# band-dsp-micro.net
KiCad netlist of a schematic drawn in EAGLE
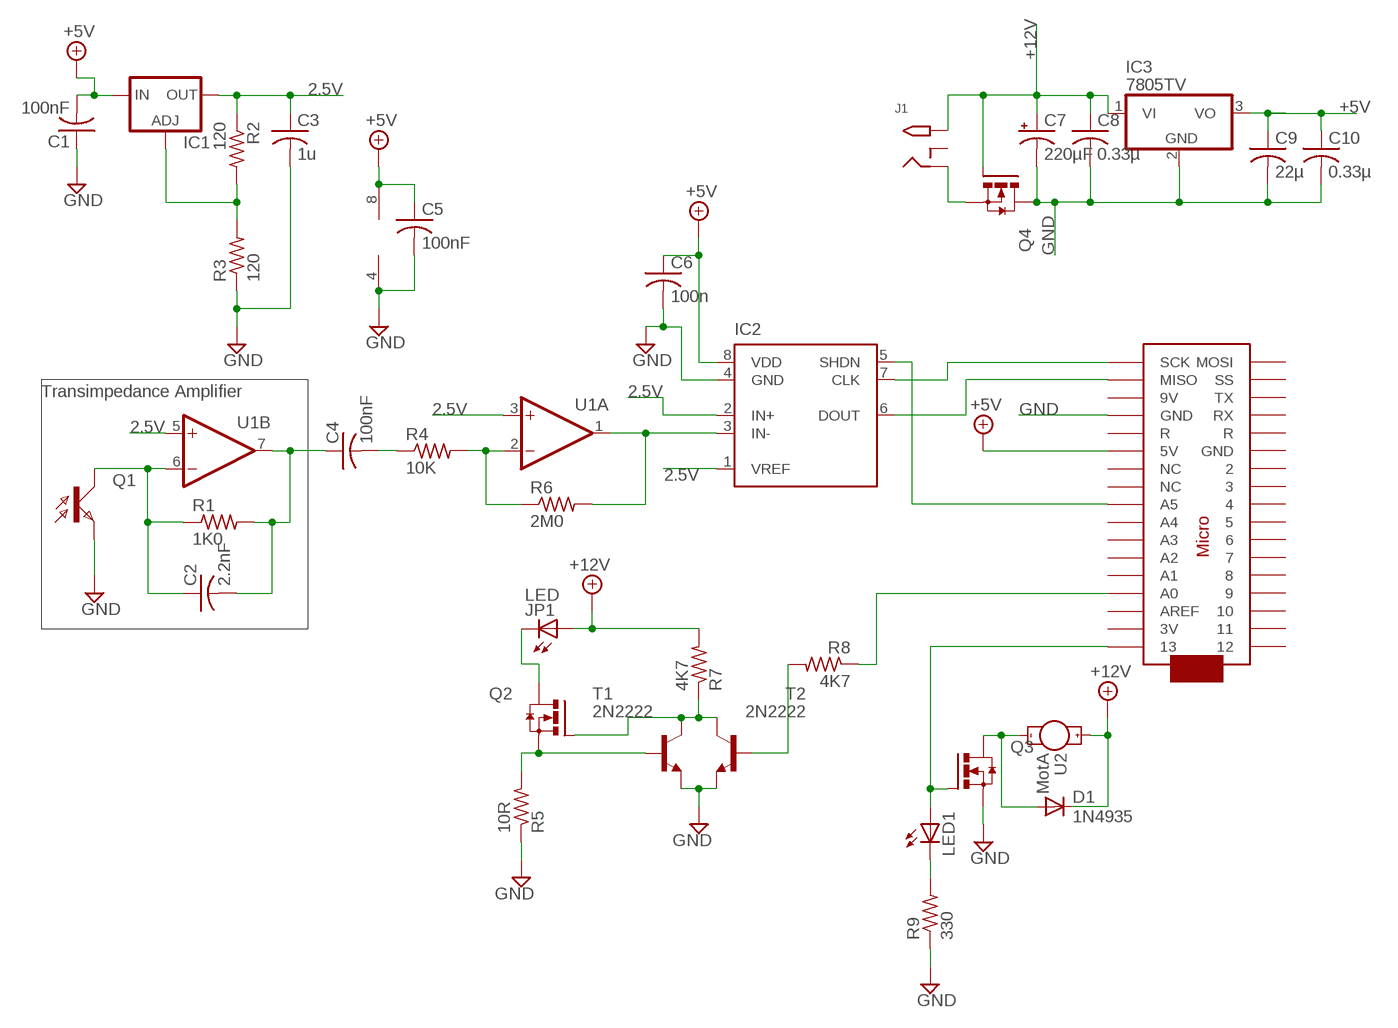
[diagram p0: schematic, sheet 1]

(export (version "E")
  (design (tool "Eeschema 10.0.6"))
  (components
    (comp (ref "C1")
      (value "100nF")
      (footprint "eagle-import:C025-025X050")
      (fields (field (name "MANF") "Vishay BC Components"))
      (libsource (lib "eagle-import") (part "C-US025-025X050"))
    )
    (comp (ref "C2")
      (value "2.2nF")
      (footprint "eagle-import:C025-024X044")
      (fields (field (name "MANF") "Vishay BC Components"))
      (libsource (lib "eagle-import") (part "C-US025-024X044"))
    )
    (comp (ref "C3")
      (value "1u")
      (footprint "eagle-import:C050-024X044")
      (fields (field (name "MANF") "TDK Corporation"))
      (libsource (lib "eagle-import") (part "C-US050-024X044"))
    )
    (comp (ref "C4")
      (value "100nF")
      (footprint "eagle-import:C025-060X050")
      (fields (field (name "MANF") "TDK Corporation"))
      (libsource (lib "eagle-import") (part "C-US025-060X050"))
    )
    (comp (ref "C5")
      (value "100nF")
      (footprint "eagle-import:C025-025X050")
      (libsource (lib "eagle-import") (part "C-US025-025X050"))
    )
    (comp (ref "C6")
      (value "100n")
      (footprint "eagle-import:C025-025X050")
      (libsource (lib "eagle-import") (part "C-US025-025X050"))
    )
    (comp (ref "C7")
      (value "220µF")
      (footprint "eagle-import:E3,5-8")
      (fields (field (name "MANF") "Panasonic Electronic Components"))
      (libsource (lib "eagle-import") (part "CPOL-USE3.5-8"))
    )
    (comp (ref "C8")
      (value "0.33µ")
      (footprint "eagle-import:C025-050X050")
      (fields (field (name "MANF") "TDK Corporation"))
      (libsource (lib "eagle-import") (part "C-US025-050X050"))
    )
    (comp (ref "C9")
      (value "22µ")
      (footprint "eagle-import:C050-045X075")
      (fields (field (name "MANF") "TDK Corporation"))
      (libsource (lib "eagle-import") (part "C-US050-045X075"))
    )
    (comp (ref "C10")
      (value "0.33µ")
      (footprint "eagle-import:C025-050X050")
      (fields (field (name "MANF") "TDK Corporation"))
      (libsource (lib "eagle-import") (part "C-US025-050X050"))
    )
    (comp (ref "D1")
      (value "1N4935")
      (footprint "eagle-import:DO41-10")
      (fields (field (name "MANF") "Fairchild Semiconductor"))
      (libsource (lib "eagle-import") (part "1N4004"))
    )
    (comp (ref "IC1")
      (value "LM317L")
      (footprint "eagle-import:317L")
      (fields (field (name "MANF") "Texas Instruments"))
      (libsource (lib "eagle-import") (part "LM317L"))
    )
    (comp (ref "IC2")
      (value "MCP3301")
      (footprint "eagle-import:DIL08")
      (fields (field (name "MANF") "Microchip Technology"))
      (libsource (lib "eagle-import") (part "MCP3301"))
    )
    (comp (ref "IC3")
      (value "7805TV")
      (footprint "eagle-import:TO220V")
      (fields (field (name "MANF") "Fairchild Semiconductor"))
      (libsource (lib "eagle-import") (part "78TV05"))
    )
    (comp (ref "J1")
      (value "2.1MMJACKTHM")
      (footprint "eagle-import:PJ-102A")
      (fields (field (name "MANF") "CUI Inc"))
      (libsource (lib "eagle-import") (part "2.1MMJACKTHM"))
    )
    (comp (ref "JP1")
      (value "LED")
      (footprint "eagle-import:1X02_SCREW")
      (fields (field (name "MANF") "OSRAM Opto Semiconductors Inc"))
      (libsource (lib "eagle-import") (part "LED_CXN"))
    )
    (comp (ref "LED1")
      (value "LED3MM")
      (footprint "eagle-import:LED3MM")
      (fields (field (name "MANF") "Lite-On Inc"))
      (libsource (lib "eagle-import") (part "LED3MM"))
    )
    (comp (ref "Q1")
      (value "LTR-4206")
      (footprint "eagle-import:3MM_LED")
      (fields (field (name "MANF") "Lite-On Inc"))
      (libsource (lib "eagle-import") (part "LTR-4206"))
    )
    (comp (ref "Q2")
      (value "IRLB8721")
      (footprint "eagle-import:TO220BV")
      (libsource (lib "eagle-import") (part "IRLB8721"))
    )
    (comp (ref "Q3")
      (value "IRLB8721")
      (footprint "eagle-import:TO220BV")
      (fields (field (name "MANF") "International Rectifier"))
      (libsource (lib "eagle-import") (part "IRLB8721"))
    )
    (comp (ref "Q4")
      (value "IRLB8721")
      (footprint "eagle-import:TO220BV")
      (fields (field (name "MANF") "International Rectifier"))
      (libsource (lib "eagle-import") (part "IRLB8721"))
    )
    (comp (ref "R1")
      (value "1K0")
      (footprint "eagle-import:0204_5")
      (fields (field (name "MANF") "Stackpole Electronics Inc"))
      (libsource (lib "eagle-import") (part "R-US_0204/5"))
    )
    (comp (ref "R2")
      (value "120")
      (footprint "eagle-import:0204V")
      (fields (field (name "MANF") "Stackpole Electronics Inc"))
      (libsource (lib "eagle-import") (part "R-US_0204/2V"))
    )
    (comp (ref "R3")
      (value "120")
      (footprint "eagle-import:0204V")
      (fields (field (name "MANF") "Stackpole Electronics Inc"))
      (libsource (lib "eagle-import") (part "R-US_0204/2V"))
    )
    (comp (ref "R4")
      (value "10K")
      (footprint "eagle-import:0204_5")
      (fields (field (name "MANF") "Stackpole Electronics Inc"))
      (libsource (lib "eagle-import") (part "R-US_0204/5"))
    )
    (comp (ref "R5")
      (value "10R")
      (footprint "eagle-import:0204V")
      (fields (field (name "DIGIKEY#") "PPC10W-1CT-ND") (field (name "MANF") "Vishay BC Components"))
      (libsource (lib "eagle-import") (part "R-US_0204/2V"))
    )
    (comp (ref "R6")
      (value "2M0")
      (footprint "eagle-import:0309V")
      (fields (field (name "MANF") "Stackpole Electronics Inc"))
      (libsource (lib "eagle-import") (part "R-US_0309/V"))
    )
    (comp (ref "R7")
      (value "4K7")
      (footprint "eagle-import:0204V")
      (fields (field (name "MANF") "Stackpole Electronics Inc"))
      (libsource (lib "eagle-import") (part "R-US_0204/2V"))
    )
    (comp (ref "R8")
      (value "4K7")
      (footprint "eagle-import:0204V")
      (fields (field (name "MANF") "Stackpole Electronics Inc"))
      (libsource (lib "eagle-import") (part "R-US_0204/2V"))
    )
    (comp (ref "R9")
      (value "330")
      (footprint "eagle-import:0204V")
      (fields (field (name "MANF") "Stackpole Electronics Inc"))
      (libsource (lib "eagle-import") (part "R-US_0204/2V"))
    )
    (comp (ref "T1")
      (value "2N2222")
      (footprint "eagle-import:TO92-EBC-OVAL")
      (fields (field (name "MANF") "Fairchild Semiconductor"))
      (libsource (lib "eagle-import") (part "2N2222"))
    )
    (comp (ref "T2")
      (value "2N2222")
      (footprint "eagle-import:TO92-EBC-OVAL")
      (fields (field (name "MANF") "Fairchild Semiconductor"))
      (libsource (lib "eagle-import") (part "2N2222"))
    )
    (comp (ref "U1")
      (value "LMC6482")
      (footprint "eagle-import:DIL08")
      (fields
        (field (name "DIGIKEY#") "LMC6482AIN/NOPB-ND")
        (field (name "DIGIKEY2#") "AE9986-ND")
        (field (name "MANF") "Texas Instruments")
        (field (name "MANF#") "LMC6482AIN/NOPB")
      )
      (libsource (lib "eagle-import") (part "LMC6482"))
    )
    (comp (ref "U2")
      (value "MotA")
      (footprint "eagle-import:1X02_SCREW")
      (fields (field (name "MANF") "Switchcraft Inc."))
      (libsource (lib "eagle-import") (part "1X02_MOTOR"))
    )
    (comp (ref "U3")
      (value "ARDUINOMICRO")
      (footprint "eagle-import:ARDUINOMICRO")
      (fields (field (name "MANF") "Arduino"))
      (libsource (lib "eagle-import") (part "ARDUINOMICRO"))
    )
  )
  (nets
    (net (code "1") (name "+5V") (class "Default")
      (node (ref "C1") (pin "2") (pinfunction "2_2") (pintype "passive"))
      (node (ref "C10") (pin "1") (pinfunction "1_1") (pintype "passive"))
      (node (ref "C5") (pin "1") (pinfunction "1_1") (pintype "passive"))
      (node (ref "C6") (pin "1") (pinfunction "1_1") (pintype "passive"))
      (node (ref "C9") (pin "1") (pinfunction "1_1") (pintype "passive"))
      (node (ref "IC1") (pin "3") (pinfunction "IN_3") (pintype "input"))
      (node (ref "IC2") (pin "8") (pinfunction "VDD_8") (pintype "power_in"))
      (node (ref "IC3") (pin "3") (pinfunction "VO_3") (pintype "passive"))
      (node (ref "U1") (pin "8") (pinfunction "V+_8") (pintype "power_in"))
      (node (ref "U3") (pin "P$23") (pinfunction "5V_P$23") (pintype "bidirectional"))
    )
    (net (code "2") (name "+12V") (class "Default")
      (node (ref "C7") (pin "+") (pinfunction "+_+") (pintype "passive"))
      (node (ref "C8") (pin "1") (pinfunction "1_1") (pintype "passive"))
      (node (ref "D1") (pin "C") (pinfunction "C_C") (pintype "passive"))
      (node (ref "IC3") (pin "1") (pinfunction "VI_1") (pintype "input"))
      (node (ref "J1") (pin "TIP") (pinfunction "TIP_TIP") (pintype "bidirectional"))
      (node (ref "JP1") (pin "1/POS") (pinfunction "A_1/POS") (pintype "passive"))
      (node (ref "Q4") (pin "G") (pinfunction "G_G") (pintype "passive"))
      (node (ref "R7") (pin "2") (pinfunction "2_2") (pintype "passive"))
      (node (ref "U2") (pin "1/POS") (pinfunction "+_1/POS") (pintype "bidirectional"))
    )
    (net (code "3") (name "/2.5V") (class "Default")
      (node (ref "C3") (pin "1") (pinfunction "1_1") (pintype "passive"))
      (node (ref "IC1") (pin "2") (pinfunction "OUT_2") (pintype "passive"))
      (node (ref "IC2") (pin "1") (pinfunction "VREF_1") (pintype "input"))
      (node (ref "IC2") (pin "2") (pinfunction "IN+_2") (pintype "input"))
      (node (ref "R2") (pin "1") (pinfunction "1_1") (pintype "passive"))
      (node (ref "U1") (pin "3") (pinfunction "+IN_3") (pintype "input"))
      (node (ref "U1") (pin "5") (pinfunction "+IN_5") (pintype "input"))
    )
    (net (code "4") (name "GND") (class "Default")
      (node (ref "C1") (pin "1") (pinfunction "1_1") (pintype "passive"))
      (node (ref "C10") (pin "2") (pinfunction "2_2") (pintype "passive"))
      (node (ref "C3") (pin "2") (pinfunction "2_2") (pintype "passive"))
      (node (ref "C5") (pin "2") (pinfunction "2_2") (pintype "passive"))
      (node (ref "C6") (pin "2") (pinfunction "2_2") (pintype "passive"))
      (node (ref "C7") (pin "-") (pinfunction "-_-") (pintype "passive"))
      (node (ref "C8") (pin "2") (pinfunction "2_2") (pintype "passive"))
      (node (ref "C9") (pin "2") (pinfunction "2_2") (pintype "passive"))
      (node (ref "IC2") (pin "4") (pinfunction "GND_4") (pintype "power_in"))
      (node (ref "IC3") (pin "2") (pinfunction "GND_2") (pintype "passive"))
      (node (ref "Q1") (pin "A") (pinfunction "E_A") (pintype "passive"))
      (node (ref "Q3") (pin "S") (pinfunction "S_S") (pintype "passive"))
      (node (ref "Q4") (pin "D") (pinfunction "D_D") (pintype "passive"))
      (node (ref "R3") (pin "1") (pinfunction "1_1") (pintype "passive"))
      (node (ref "R5") (pin "1") (pinfunction "1_1") (pintype "passive"))
      (node (ref "R9") (pin "1") (pinfunction "1_1") (pintype "passive"))
      (node (ref "T1") (pin "E") (pinfunction "E_E") (pintype "passive"))
      (node (ref "T2") (pin "E") (pinfunction "E_E") (pintype "passive"))
      (node (ref "U1") (pin "4") (pinfunction "V-_4") (pintype "power_in"))
      (node (ref "U3") (pin "P$12") (pinfunction "GND_P$12") (pintype "bidirectional"))
    )
    (net (code "5") (name "Net-(C4-Pad2)") (class "Default")
      (node (ref "C4") (pin "2") (pinfunction "2_2") (pintype "passive"))
      (node (ref "R4") (pin "1") (pinfunction "1_1") (pintype "passive"))
    )
    (net (code "6") (name "Net-(IC1-ADJ)") (class "Default")
      (node (ref "IC1") (pin "1") (pinfunction "ADJ_1") (pintype "input"))
      (node (ref "R2") (pin "2") (pinfunction "2_2") (pintype "passive"))
      (node (ref "R3") (pin "2") (pinfunction "2_2") (pintype "passive"))
    )
    (net (code "7") (name "Net-(IC2-CLK)") (class "Default")
      (node (ref "IC2") (pin "7") (pinfunction "CLK_7") (pintype "input"))
      (node (ref "U3") (pin "P$18") (pinfunction "SCK_P$18") (pintype "bidirectional"))
    )
    (net (code "8") (name "Net-(IC2-DOUT)") (class "Default")
      (node (ref "IC2") (pin "6") (pinfunction "DOUT_6") (pintype "input"))
      (node (ref "U3") (pin "P$19") (pinfunction "MISO_P$19") (pintype "bidirectional"))
    )
    (net (code "9") (name "Net-(IC2-IN-)") (class "Default")
      (node (ref "IC2") (pin "3") (pinfunction "IN-_3") (pintype "input"))
      (node (ref "R6") (pin "2") (pinfunction "2_2") (pintype "passive"))
      (node (ref "U1") (pin "1") (pinfunction "OUT_1") (pintype "output"))
    )
    (net (code "10") (name "Net-(IC2-SHDN)") (class "Default")
      (node (ref "IC2") (pin "5") (pinfunction "SHDN_5") (pintype "input"))
      (node (ref "U3") (pin "P$26") (pinfunction "A5_P$26") (pintype "bidirectional"))
    )
    (net (code "11") (name "Net-(J1-PadRING)") (class "Default")
      (node (ref "J1") (pin "RING") (pinfunction "RING_RING") (pintype "bidirectional"))
      (node (ref "Q4") (pin "S") (pinfunction "S_S") (pintype "passive"))
    )
    (net (code "12") (name "Net-(JP1-K)") (class "Default")
      (node (ref "JP1") (pin "2") (pinfunction "K_2") (pintype "passive"))
      (node (ref "Q2") (pin "D") (pinfunction "D_D") (pintype "passive"))
    )
    (net (code "13") (name "Net-(LED1-C)") (class "Default")
      (node (ref "LED1") (pin "K") (pinfunction "C_K") (pintype "passive"))
      (node (ref "R9") (pin "2") (pinfunction "2_2") (pintype "passive"))
    )
    (net (code "14") (name "Net-(Q1-C)") (class "Default")
      (node (ref "C2") (pin "1") (pinfunction "1_1") (pintype "passive"))
      (node (ref "Q1") (pin "K") (pinfunction "C_K") (pintype "passive"))
      (node (ref "R1") (pin "1") (pinfunction "1_1") (pintype "passive"))
      (node (ref "U1") (pin "6") (pinfunction "-IN_6") (pintype "input"))
    )
    (net (code "15") (name "Net-(Q2-PadG)") (class "Default")
      (node (ref "Q2") (pin "G") (pinfunction "G_G") (pintype "passive"))
      (node (ref "R7") (pin "1") (pinfunction "1_1") (pintype "passive"))
      (node (ref "T1") (pin "C") (pinfunction "C_C") (pintype "passive"))
      (node (ref "T2") (pin "C") (pinfunction "C_C") (pintype "passive"))
    )
    (net (code "16") (name "Net-(Q2-PadS)") (class "Default")
      (node (ref "Q2") (pin "S") (pinfunction "S_S") (pintype "passive"))
      (node (ref "R5") (pin "2") (pinfunction "2_2") (pintype "passive"))
      (node (ref "T1") (pin "B") (pinfunction "B_B") (pintype "passive"))
    )
    (net (code "17") (name "Net-(R8-Pad2)") (class "Default")
      (node (ref "R8") (pin "2") (pinfunction "2_2") (pintype "passive"))
      (node (ref "T2") (pin "B") (pinfunction "B_B") (pintype "passive"))
    )
    (net (code "18") (name "Net-(U1A--IN)") (class "Default")
      (node (ref "R4") (pin "2") (pinfunction "2_2") (pintype "passive"))
      (node (ref "R6") (pin "1") (pinfunction "1_1") (pintype "passive"))
      (node (ref "U1") (pin "2") (pinfunction "-IN_2") (pintype "input"))
    )
    (net (code "19") (name "Net-(U1B-OUT)") (class "Default")
      (node (ref "C2") (pin "2") (pinfunction "2_2") (pintype "passive"))
      (node (ref "C4") (pin "1") (pinfunction "1_1") (pintype "passive"))
      (node (ref "R1") (pin "2") (pinfunction "2_2") (pintype "passive"))
      (node (ref "U1") (pin "7") (pinfunction "OUT_7") (pintype "output"))
    )
    (net (code "20") (name "Net-(U2--)") (class "Default")
      (node (ref "D1") (pin "A") (pinfunction "A_A") (pintype "passive"))
      (node (ref "Q3") (pin "D") (pinfunction "D_D") (pintype "passive"))
      (node (ref "U2") (pin "2") (pinfunction "-_2") (pintype "bidirectional"))
    )
    (net (code "21") (name "Net-(U3-13)") (class "Default")
      (node (ref "LED1") (pin "A") (pinfunction "A_A") (pintype "passive"))
      (node (ref "Q3") (pin "G") (pinfunction "G_G") (pintype "passive"))
      (node (ref "U3") (pin "P$34") (pinfunction "13_P$34") (pintype "bidirectional"))
    )
    (net (code "22") (name "Net-(U3-A0)") (class "Default")
      (node (ref "R8") (pin "1") (pinfunction "1_1") (pintype "passive"))
      (node (ref "U3") (pin "P$31") (pinfunction "A0_P$31") (pintype "bidirectional"))
    )
    (net (code "23") (name "unconnected-(J1-PadRING_SW)") (class "Default")
      (node (ref "J1") (pin "RING_SW") (pinfunction "RING_SW_RING_SW") (pintype "bidirectional"))
    )
    (net (code "24") (name "unconnected-(U3-2-PadP$11)") (class "Default")
      (node (ref "U3") (pin "P$11") (pinfunction "2_P$11") (pintype "bidirectional"))
    )
    (net (code "25") (name "unconnected-(U3-3-PadP$10)") (class "Default")
      (node (ref "U3") (pin "P$10") (pinfunction "3_P$10") (pintype "bidirectional"))
    )
    (net (code "26") (name "unconnected-(U3-3V-PadP$33)") (class "Default")
      (node (ref "U3") (pin "P$33") (pinfunction "3V_P$33") (pintype "bidirectional"))
    )
    (net (code "27") (name "unconnected-(U3-4-PadP$9)") (class "Default")
      (node (ref "U3") (pin "P$9") (pinfunction "4_P$9") (pintype "bidirectional"))
    )
    (net (code "28") (name "unconnected-(U3-5-PadP$8)") (class "Default")
      (node (ref "U3") (pin "P$8") (pinfunction "5_P$8") (pintype "bidirectional"))
    )
    (net (code "29") (name "unconnected-(U3-6-PadP$7)") (class "Default")
      (node (ref "U3") (pin "P$7") (pinfunction "6_P$7") (pintype "bidirectional"))
    )
    (net (code "30") (name "unconnected-(U3-7-PadP$6)") (class "Default")
      (node (ref "U3") (pin "P$6") (pinfunction "7_P$6") (pintype "bidirectional"))
    )
    (net (code "31") (name "unconnected-(U3-8-PadP$5)") (class "Default")
      (node (ref "U3") (pin "P$5") (pinfunction "8_P$5") (pintype "bidirectional"))
    )
    (net (code "32") (name "unconnected-(U3-9-PadP$4)") (class "Default")
      (node (ref "U3") (pin "P$4") (pinfunction "9_P$4") (pintype "bidirectional"))
    )
    (net (code "33") (name "unconnected-(U3-9V-PadP$20)") (class "Default")
      (node (ref "U3") (pin "P$20") (pinfunction "9V_P$20") (pintype "bidirectional"))
    )
    (net (code "34") (name "unconnected-(U3-10-PadP$3)") (class "Default")
      (node (ref "U3") (pin "P$3") (pinfunction "10_P$3") (pintype "bidirectional"))
    )
    (net (code "35") (name "unconnected-(U3-11-PadP$2)") (class "Default")
      (node (ref "U3") (pin "P$2") (pinfunction "11_P$2") (pintype "bidirectional"))
    )
    (net (code "36") (name "unconnected-(U3-12-PadP$1)") (class "Default")
      (node (ref "U3") (pin "P$1") (pinfunction "12_P$1") (pintype "bidirectional"))
    )
    (net (code "37") (name "unconnected-(U3-A1-PadP$30)") (class "Default")
      (node (ref "U3") (pin "P$30") (pinfunction "A1_P$30") (pintype "bidirectional"))
    )
    (net (code "38") (name "unconnected-(U3-A2-PadP$29)") (class "Default")
      (node (ref "U3") (pin "P$29") (pinfunction "A2_P$29") (pintype "bidirectional"))
    )
    (net (code "39") (name "unconnected-(U3-A3-PadP$28)") (class "Default")
      (node (ref "U3") (pin "P$28") (pinfunction "A3_P$28") (pintype "bidirectional"))
    )
    (net (code "40") (name "unconnected-(U3-A4-PadP$27)") (class "Default")
      (node (ref "U3") (pin "P$27") (pinfunction "A4_P$27") (pintype "bidirectional"))
    )
    (net (code "41") (name "unconnected-(U3-AREF-PadP$32)") (class "Default")
      (node (ref "U3") (pin "P$32") (pinfunction "AREF_P$32") (pintype "bidirectional"))
    )
    (net (code "42") (name "unconnected-(U3-GND-PadP$21)") (class "Default")
      (node (ref "U3") (pin "P$21") (pinfunction "GND_P$21") (pintype "bidirectional"))
    )
    (net (code "43") (name "unconnected-(U3-MOSI-PadP$17)") (class "Default")
      (node (ref "U3") (pin "P$17") (pinfunction "MOSI_P$17") (pintype "bidirectional"))
    )
    (net (code "44") (name "unconnected-(U3-NC-PadP$24)") (class "Default")
      (node (ref "U3") (pin "P$24") (pinfunction "NC_P$24") (pintype "bidirectional"))
    )
    (net (code "45") (name "unconnected-(U3-NC-PadP$25)") (class "Default")
      (node (ref "U3") (pin "P$25") (pinfunction "NC_P$25") (pintype "bidirectional"))
    )
    (net (code "46") (name "unconnected-(U3-R-PadP$13)") (class "Default")
      (node (ref "U3") (pin "P$13") (pinfunction "R_P$13") (pintype "bidirectional"))
    )
    (net (code "47") (name "unconnected-(U3-R-PadP$22)") (class "Default")
      (node (ref "U3") (pin "P$22") (pinfunction "R_P$22") (pintype "bidirectional"))
    )
    (net (code "48") (name "unconnected-(U3-RX-PadP$14)") (class "Default")
      (node (ref "U3") (pin "P$14") (pinfunction "RX_P$14") (pintype "bidirectional"))
    )
    (net (code "49") (name "unconnected-(U3-SS-PadP$16)") (class "Default")
      (node (ref "U3") (pin "P$16") (pinfunction "SS_P$16") (pintype "bidirectional"))
    )
    (net (code "50") (name "unconnected-(U3-TX-PadP$15)") (class "Default")
      (node (ref "U3") (pin "P$15") (pinfunction "TX_P$15") (pintype "bidirectional"))
    )
  )
)
